# Schematic.net
KiCad netlist of a schematic drawn in EasyEDA
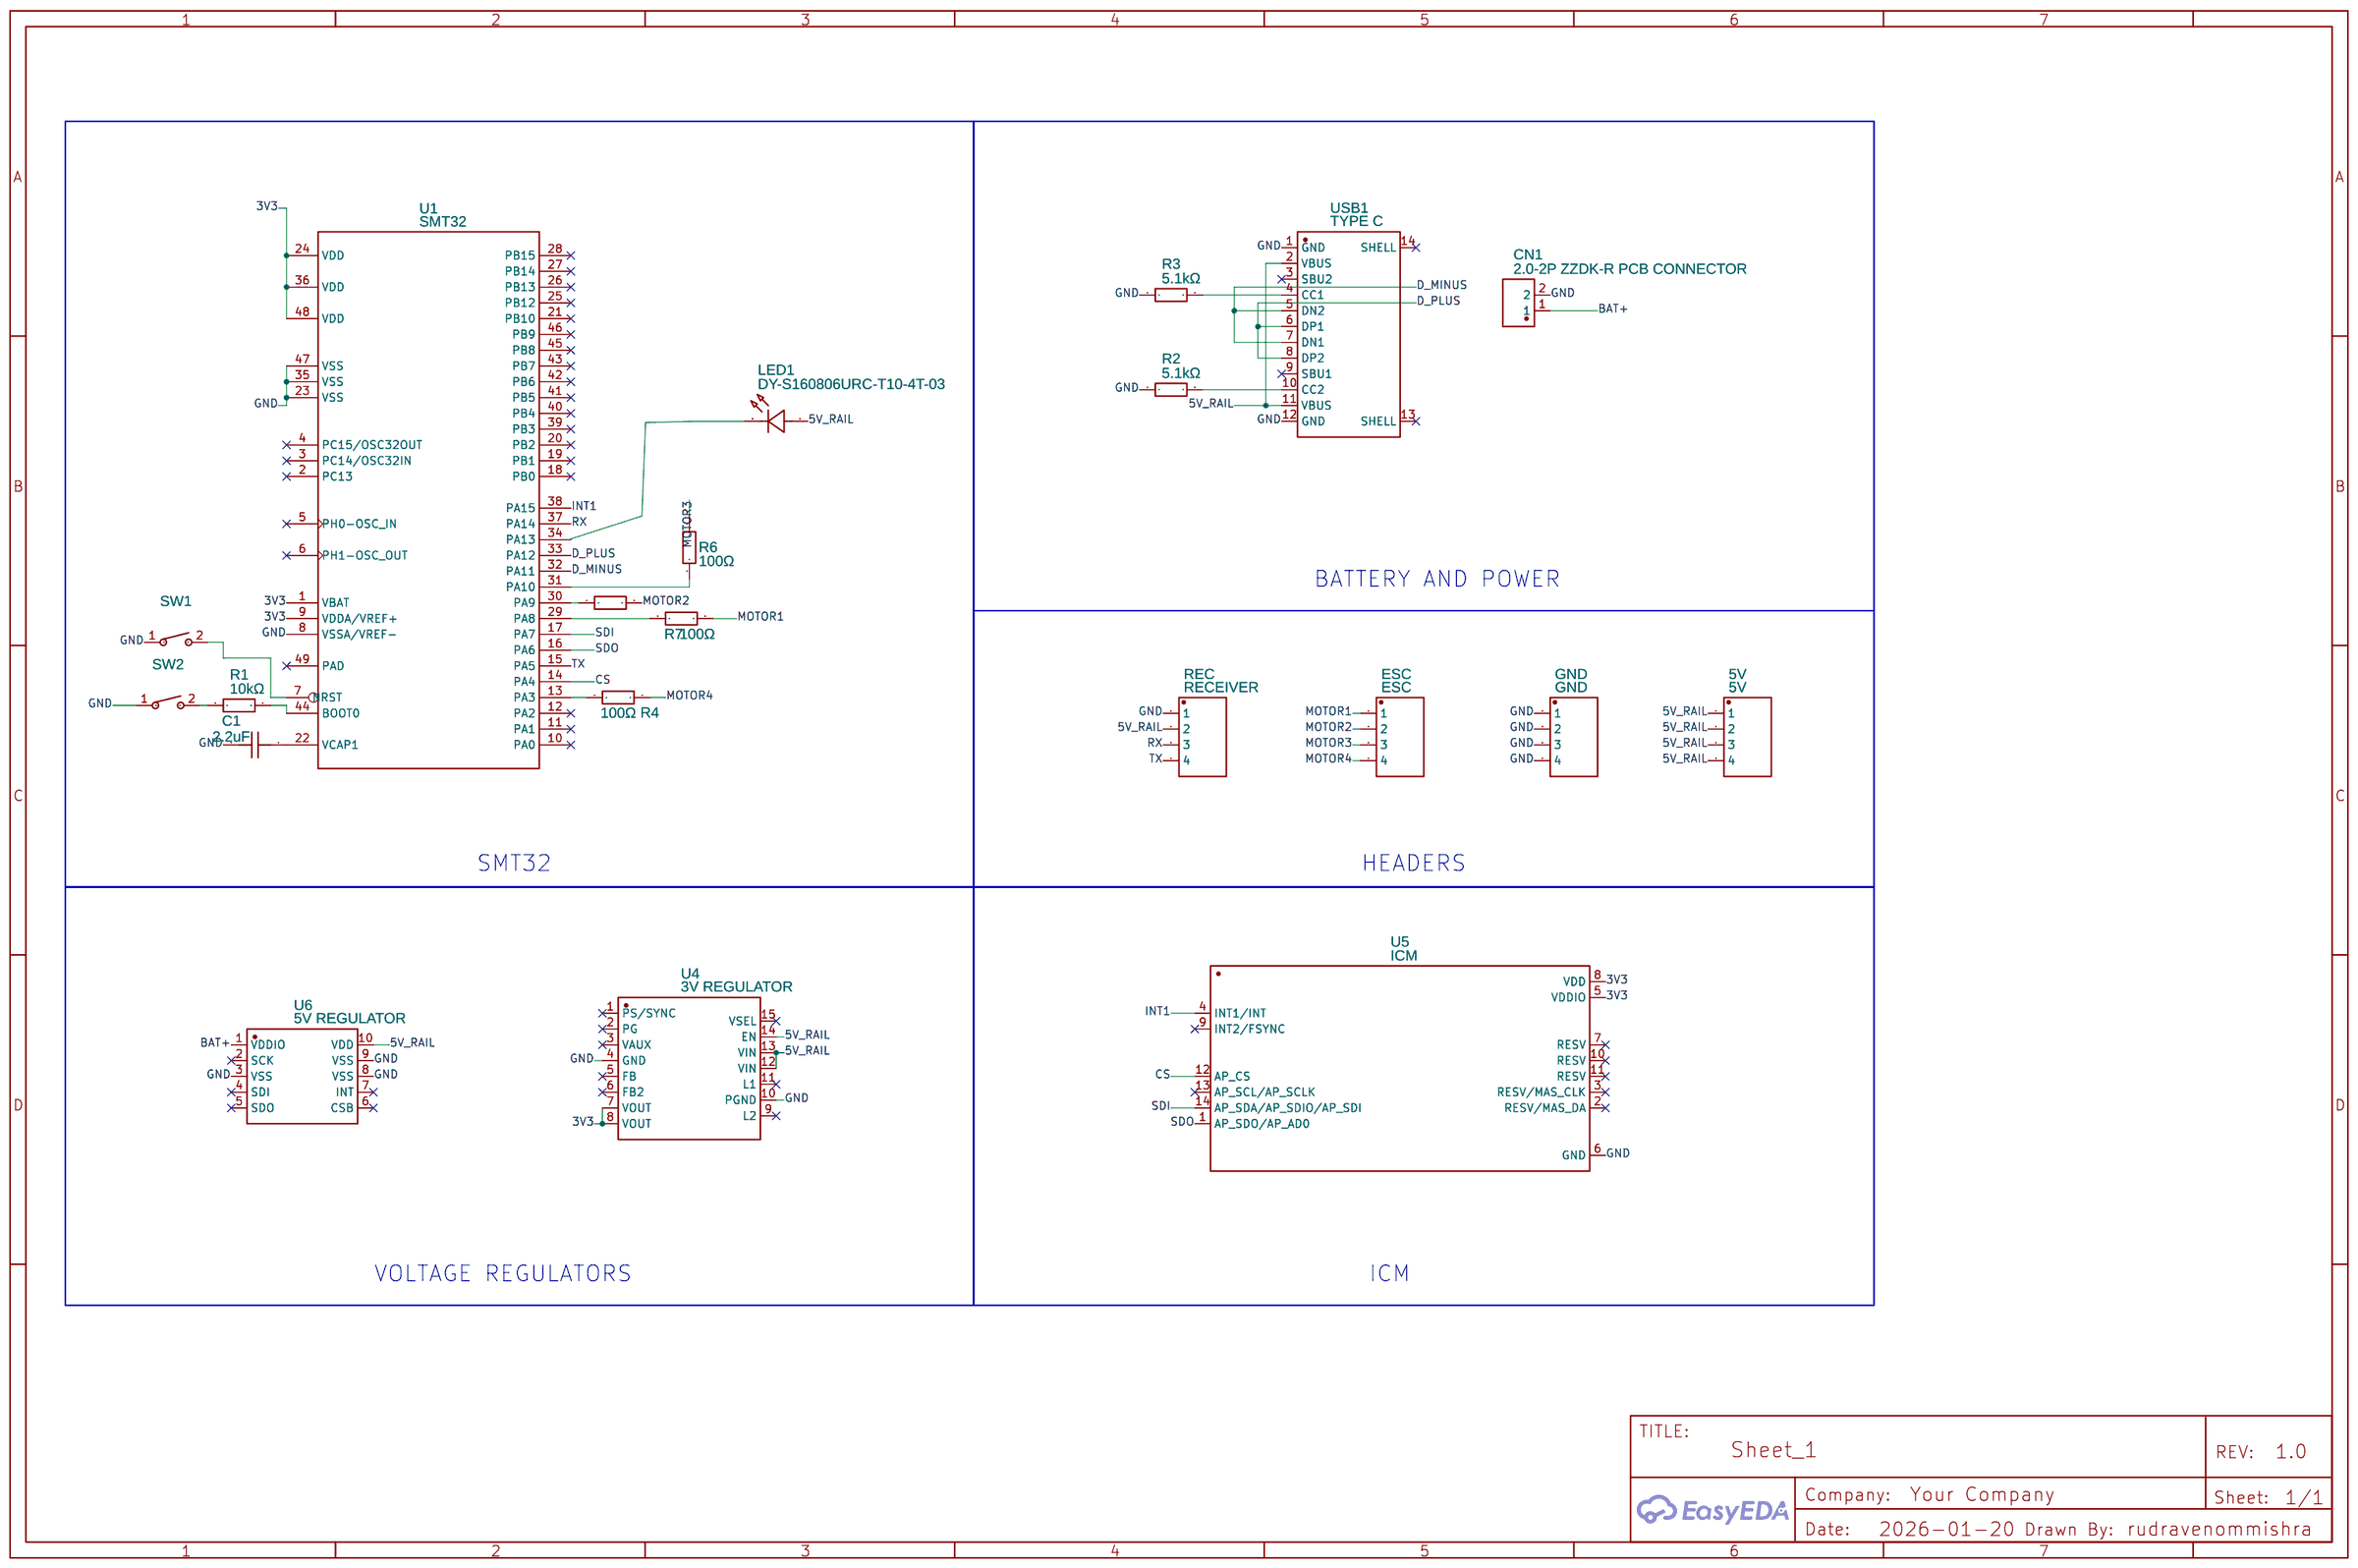
[diagram p0: schematic sheet]

(export (version "E")
  (design (tool "Eeschema 10.0.6"))
  (components
    (comp (ref "5V")
      (value "5V")
      (fields (field (name "Manufacturer Part") "B-2100S04P-A110") (field (name "Manufacturer") "Ckmtw(灿科盟)"))
      (libsource (lib "") (part "Header-Male-2.54_1x4"))
    )
    (comp (ref "C1")
      (value "2.2uF")
      (fields (field (name "Manufacturer Part") "1206X225K250NT") (field (name "Manufacturer") "FH(风华)"))
      (libsource (lib "") (part "1206X225K250NT"))
    )
    (comp (ref "CN1")
      (value "2.0-2P ZZDK-R PCB CONNECTOR")
      (fields
        (field (name "Manufacturer Part") "2.0-2P ZZDK-R PCB Connector")
        (field (name "Manufacturer") "SHOU HAN(首韩)")
      )
      (libsource (lib "") (part "2.0-2P ZZDK-R PCB CONNECTOR"))
    )
    (comp (ref "ESC")
      (value "ESC")
      (fields (field (name "Manufacturer Part") "B-2100S04P-A110") (field (name "Manufacturer") "Ckmtw(灿科盟)"))
      (libsource (lib "") (part "Header-Male-2.54_1x4_2"))
    )
    (comp (ref "GND")
      (value "GND")
      (fields (field (name "Manufacturer Part") "B-2100S04P-A110") (field (name "Manufacturer") "Ckmtw(灿科盟)"))
      (libsource (lib "") (part "Header-Male-2.54_1x4_1"))
    )
    (comp (ref "LED1")
      (value "DY-S160806URC-T10-4T-03")
      (fields (field (name "Manufacturer") "TONYU(东裕)"))
      (libsource (lib "") (part "DY-S160806URC-T10-4T-03"))
    )
    (comp (ref "R1")
      (value "10kΩ")
      (fields (field (name "Manufacturer Part") "PTFR0805B10K0P9") (field (name "Manufacturer") "RESI(开步睿思)"))
      (libsource (lib "") (part "PTFR0805B10K0P9"))
    )
    (comp (ref "R2")
      (value "5.1kΩ")
      (fields
        (field (name "Manufacturer Part") "0402WGF5101TCE")
        (field (name "Manufacturer") "UNI-ROYAL(厚声)")
      )
      (libsource (lib "") (part "0402WGF5101TCE"))
    )
    (comp (ref "R3")
      (value "5.1kΩ")
      (fields
        (field (name "Manufacturer Part") "0402WGF5101TCE")
        (field (name "Manufacturer") "UNI-ROYAL(厚声)")
      )
      (libsource (lib "") (part "0402WGF5101TCE"))
    )
    (comp (ref "R4")
      (value "100Ω")
      (fields
        (field (name "Manufacturer Part") "0105WHF1000TDE")
        (field (name "Manufacturer") "UNI-ROYAL(厚声)")
      )
      (libsource (lib "") (part "0105WHF1000TDE"))
    )
    (comp (ref "R5")
      (value "100Ω")
      (fields
        (field (name "Manufacturer Part") "0105WHF1000TDE")
        (field (name "Manufacturer") "UNI-ROYAL(厚声)")
      )
      (libsource (lib "") (part "0105WHF1000TDE"))
    )
    (comp (ref "R6")
      (value "100Ω")
      (fields
        (field (name "Manufacturer Part") "0105WHF1000TDE")
        (field (name "Manufacturer") "UNI-ROYAL(厚声)")
      )
      (libsource (lib "") (part "0105WHF1000TDE_1"))
    )
    (comp (ref "R7")
      (value "100Ω")
      (fields
        (field (name "Manufacturer Part") "0105WHF1000TDE")
        (field (name "Manufacturer") "UNI-ROYAL(厚声)")
      )
      (libsource (lib "") (part "0105WHF1000TDE"))
    )
    (comp (ref "REC")
      (value "RECEIVER")
      (fields (field (name "Manufacturer Part") "B-2100S04P-A110") (field (name "Manufacturer") "Ckmtw(灿科盟)"))
      (libsource (lib "") (part "Header-Male-2.54_1x4_3"))
    )
    (comp (ref "SW1")
      (value "HX 3X4X2-2P-1.6N TACTILE SWITCH")
      (fields
        (field (name "Manufacturer Part") "HX 3x4x2-2P-1.6N TACTILE SWITCH")
        (field (name "Manufacturer") "hanxia(韩下)")
      )
      (libsource (lib "") (part "HX 3X4X2-2P-1.6N TACTILE SWITCH"))
    )
    (comp (ref "SW2")
      (value "HX 3X4X2-2P-1.6N TACTILE SWITCH")
      (fields
        (field (name "Manufacturer Part") "HX 3x4x2-2P-1.6N TACTILE SWITCH")
        (field (name "Manufacturer") "hanxia(韩下)")
      )
      (libsource (lib "") (part "HX 3X4X2-2P-1.6N TACTILE SWITCH"))
    )
    (comp (ref "U1")
      (value "SMT32")
      (fields (field (name "Manufacturer Part") "STM32F411CEU6") (field (name "Manufacturer") "ST(意法半导体)"))
      (libsource (lib "") (part "STM32F411CEU6"))
    )
    (comp (ref "U4")
      (value "3V REGULATOR")
      (fields (field (name "Manufacturer Part") "TPS630701RNMR") (field (name "Manufacturer") "TI(德州仪器)"))
      (libsource (lib "") (part "TPS630701RNMR"))
    )
    (comp (ref "U5")
      (value "ICM")
      (fields
        (field (name "Manufacturer Part") "ICM-45605")
        (field (name "Manufacturer") "TDK InvenSense(应美盛)")
      )
      (libsource (lib "") (part "ICM-45605"))
    )
    (comp (ref "U6")
      (value "5V REGULATOR")
      (fields (field (name "Manufacturer Part") "BMP580") (field (name "Manufacturer") "Bosch(博世)"))
      (libsource (lib "") (part "BMP580"))
    )
    (comp (ref "USB1")
      (value "TYPE C")
      (fields
        (field (name "Manufacturer Part") "TYPE-C 16PIN 2MD(073)")
        (field (name "Manufacturer") "SHOU HAN(首韩)")
      )
      (libsource (lib "") (part "TYPE-C 16PIN 2MD(073)"))
    )
  )
  (nets
    (net (code "1") (name "/3V3") (class "Default")
      (node (ref "U1") (pin "1") (pinfunction "VBAT_1") (pintype "passive"))
      (node (ref "U1") (pin "24") (pinfunction "VDD_24") (pintype "unspecified"))
      (node (ref "U1") (pin "36") (pinfunction "VDD_36") (pintype "unspecified"))
      (node (ref "U1") (pin "48") (pinfunction "VDD_48") (pintype "unspecified"))
      (node (ref "U1") (pin "9") (pinfunction "VDDA/VREF+_9") (pintype "passive"))
      (node (ref "U4") (pin "7") (pinfunction "VOUT_7") (pintype "unspecified"))
      (node (ref "U4") (pin "8") (pinfunction "VOUT_8") (pintype "unspecified"))
      (node (ref "U5") (pin "5") (pinfunction "VDDIO_5") (pintype "unspecified"))
      (node (ref "U5") (pin "8") (pinfunction "VDD_8") (pintype "unspecified"))
    )
    (net (code "2") (name "/5V_RAIL") (class "Default")
      (node (ref "5V") (pin "1") (pinfunction "1_1") (pintype "unspecified"))
      (node (ref "5V") (pin "2") (pinfunction "2_2") (pintype "unspecified"))
      (node (ref "5V") (pin "3") (pinfunction "3_3") (pintype "unspecified"))
      (node (ref "5V") (pin "4") (pinfunction "4_4") (pintype "unspecified"))
      (node (ref "LED1") (pin "2") (pinfunction "A_2") (pintype "unspecified"))
      (node (ref "REC") (pin "2") (pinfunction "2_2") (pintype "unspecified"))
      (node (ref "U4") (pin "12") (pinfunction "VIN_12") (pintype "unspecified"))
      (node (ref "U4") (pin "13") (pinfunction "VIN_13") (pintype "unspecified"))
      (node (ref "U4") (pin "14") (pinfunction "EN_14") (pintype "unspecified"))
      (node (ref "U6") (pin "10") (pinfunction "VDD_10") (pintype "unspecified"))
      (node (ref "USB1") (pin "11") (pinfunction "VBUS_11") (pintype "unspecified"))
      (node (ref "USB1") (pin "2") (pinfunction "VBUS_2") (pintype "unspecified"))
    )
    (net (code "3") (name "/BAT+") (class "Default")
      (node (ref "CN1") (pin "1") (pinfunction "1_1") (pintype "unspecified"))
      (node (ref "U6") (pin "1") (pinfunction "VDDIO_1") (pintype "unspecified"))
    )
    (net (code "4") (name "/CS") (class "Default")
      (node (ref "U1") (pin "14") (pinfunction "PA4_14") (pintype "unspecified"))
      (node (ref "U5") (pin "12") (pinfunction "AP_CS_12") (pintype "unspecified"))
    )
    (net (code "5") (name "/D_MINUS") (class "Default")
      (node (ref "U1") (pin "32") (pinfunction "PA11_32") (pintype "unspecified"))
      (node (ref "USB1") (pin "5") (pinfunction "DN2_5") (pintype "unspecified"))
      (node (ref "USB1") (pin "7") (pinfunction "DN1_7") (pintype "unspecified"))
    )
    (net (code "6") (name "/D_PLUS") (class "Default")
      (node (ref "U1") (pin "33") (pinfunction "PA12_33") (pintype "unspecified"))
      (node (ref "USB1") (pin "6") (pinfunction "DP1_6") (pintype "unspecified"))
      (node (ref "USB1") (pin "8") (pinfunction "DP2_8") (pintype "unspecified"))
    )
    (net (code "7") (name "/GND") (class "Default")
      (node (ref "C1") (pin "1") (pinfunction "1_1") (pintype "unspecified"))
      (node (ref "CN1") (pin "2") (pinfunction "2_2") (pintype "unspecified"))
      (node (ref "GND") (pin "1") (pinfunction "1_1") (pintype "unspecified"))
      (node (ref "GND") (pin "2") (pinfunction "2_2") (pintype "unspecified"))
      (node (ref "GND") (pin "3") (pinfunction "3_3") (pintype "unspecified"))
      (node (ref "GND") (pin "4") (pinfunction "4_4") (pintype "unspecified"))
      (node (ref "R2") (pin "1") (pinfunction "1_1") (pintype "input"))
      (node (ref "R3") (pin "1") (pinfunction "1_1") (pintype "input"))
      (node (ref "REC") (pin "1") (pinfunction "1_1") (pintype "unspecified"))
      (node (ref "SW1") (pin "1") (pinfunction "1_1") (pintype "unspecified"))
      (node (ref "SW2") (pin "1") (pinfunction "1_1") (pintype "unspecified"))
      (node (ref "U1") (pin "23") (pinfunction "VSS_23") (pintype "unspecified"))
      (node (ref "U1") (pin "35") (pinfunction "VSS_35") (pintype "unspecified"))
      (node (ref "U1") (pin "47") (pinfunction "VSS_47") (pintype "unspecified"))
      (node (ref "U1") (pin "8") (pinfunction "VSSA/VREF-_8") (pintype "passive"))
      (node (ref "U4") (pin "10") (pinfunction "PGND_10") (pintype "unspecified"))
      (node (ref "U4") (pin "4") (pinfunction "GND_4") (pintype "unspecified"))
      (node (ref "U5") (pin "6") (pinfunction "GND_6") (pintype "unspecified"))
      (node (ref "U6") (pin "3") (pinfunction "VSS_3") (pintype "unspecified"))
      (node (ref "U6") (pin "8") (pinfunction "VSS_8") (pintype "unspecified"))
      (node (ref "U6") (pin "9") (pinfunction "VSS_9") (pintype "unspecified"))
      (node (ref "USB1") (pin "1") (pinfunction "GND_1") (pintype "unspecified"))
      (node (ref "USB1") (pin "12") (pinfunction "GND_12") (pintype "unspecified"))
    )
    (net (code "8") (name "/INT1") (class "Default")
      (node (ref "U1") (pin "38") (pinfunction "PA15_38") (pintype "unspecified"))
      (node (ref "U5") (pin "4") (pinfunction "INT1/INT_4") (pintype "unspecified"))
    )
    (net (code "9") (name "/MOTOR1") (class "Default")
      (node (ref "ESC") (pin "1") (pinfunction "1_1") (pintype "unspecified"))
      (node (ref "R7") (pin "2") (pinfunction "2_2") (pintype "unspecified"))
    )
    (net (code "10") (name "/MOTOR2") (class "Default")
      (node (ref "ESC") (pin "2") (pinfunction "2_2") (pintype "unspecified"))
      (node (ref "R5") (pin "2") (pinfunction "2_2") (pintype "unspecified"))
    )
    (net (code "11") (name "/MOTOR3") (class "Default")
      (node (ref "ESC") (pin "3") (pinfunction "3_3") (pintype "unspecified"))
      (node (ref "R6") (pin "2") (pinfunction "2_2") (pintype "unspecified"))
    )
    (net (code "12") (name "/MOTOR4") (class "Default")
      (node (ref "ESC") (pin "4") (pinfunction "4_4") (pintype "unspecified"))
      (node (ref "R4") (pin "2") (pinfunction "2_2") (pintype "unspecified"))
    )
    (net (code "13") (name "/RX") (class "Default")
      (node (ref "REC") (pin "3") (pinfunction "3_3") (pintype "unspecified"))
      (node (ref "U1") (pin "37") (pinfunction "PA14_37") (pintype "unspecified"))
    )
    (net (code "14") (name "/SDI") (class "Default")
      (node (ref "U1") (pin "17") (pinfunction "PA7_17") (pintype "unspecified"))
      (node (ref "U5") (pin "14") (pinfunction "AP_SDA/AP_SDIO/AP_SDI_14") (pintype "unspecified"))
    )
    (net (code "15") (name "/SDO") (class "Default")
      (node (ref "U1") (pin "16") (pinfunction "PA6_16") (pintype "unspecified"))
      (node (ref "U5") (pin "1") (pinfunction "AP_SDO/AP_AD0_1") (pintype "unspecified"))
    )
    (net (code "16") (name "/TX") (class "Default")
      (node (ref "REC") (pin "4") (pinfunction "4_4") (pintype "unspecified"))
      (node (ref "U1") (pin "15") (pinfunction "PA5_15") (pintype "unspecified"))
    )
    (net (code "17") (name "Net-(LED1-K)") (class "Default")
      (node (ref "LED1") (pin "1") (pinfunction "K_1") (pintype "unspecified"))
      (node (ref "U1") (pin "34") (pinfunction "PA13_34") (pintype "unspecified"))
    )
    (net (code "18") (name "Net-(R1-Pad1)") (class "Default")
      (node (ref "R1") (pin "1") (pinfunction "1_1") (pintype "input"))
      (node (ref "SW2") (pin "2") (pinfunction "2_2") (pintype "unspecified"))
    )
    (net (code "19") (name "Net-(U1-BOOT0)") (class "Default")
      (node (ref "R1") (pin "2") (pinfunction "2_2") (pintype "input"))
      (node (ref "U1") (pin "44") (pinfunction "BOOT0_44") (pintype "input"))
    )
    (net (code "20") (name "Net-(U1-NRST)") (class "Default")
      (node (ref "SW1") (pin "2") (pinfunction "2_2") (pintype "unspecified"))
      (node (ref "U1") (pin "7") (pinfunction "NRST_7") (pintype "unspecified"))
    )
    (net (code "21") (name "Net-(U1-PA3)") (class "Default")
      (node (ref "R4") (pin "1") (pinfunction "1_1") (pintype "unspecified"))
      (node (ref "U1") (pin "13") (pinfunction "PA3_13") (pintype "unspecified"))
    )
    (net (code "22") (name "Net-(U1-PA8)") (class "Default")
      (node (ref "R7") (pin "1") (pinfunction "1_1") (pintype "unspecified"))
      (node (ref "U1") (pin "29") (pinfunction "PA8_29") (pintype "unspecified"))
    )
    (net (code "23") (name "Net-(U1-PA9)") (class "Default")
      (node (ref "R5") (pin "1") (pinfunction "1_1") (pintype "unspecified"))
      (node (ref "U1") (pin "30") (pinfunction "PA9_30") (pintype "unspecified"))
    )
    (net (code "24") (name "Net-(U1-PA10)") (class "Default")
      (node (ref "R6") (pin "1") (pinfunction "1_1") (pintype "unspecified"))
      (node (ref "U1") (pin "31") (pinfunction "PA10_31") (pintype "unspecified"))
    )
    (net (code "25") (name "Net-(U1-VCAP1)") (class "Default")
      (node (ref "C1") (pin "2") (pinfunction "2_2") (pintype "unspecified"))
      (node (ref "U1") (pin "22") (pinfunction "VCAP1_22") (pintype "passive"))
    )
    (net (code "26") (name "Net-(USB1-CC1)") (class "Default")
      (node (ref "R3") (pin "2") (pinfunction "2_2") (pintype "input"))
      (node (ref "USB1") (pin "4") (pinfunction "CC1_4") (pintype "unspecified"))
    )
    (net (code "27") (name "Net-(USB1-CC2)") (class "Default")
      (node (ref "R2") (pin "2") (pinfunction "2_2") (pintype "input"))
      (node (ref "USB1") (pin "10") (pinfunction "CC2_10") (pintype "unspecified"))
    )
    (net (code "28") (name "unconnected-(U1-PA0-Pad10)") (class "Default")
      (node (ref "U1") (pin "10") (pinfunction "PA0_10") (pintype "unspecified+no_connect"))
    )
    (net (code "29") (name "unconnected-(U1-PA1-Pad11)") (class "Default")
      (node (ref "U1") (pin "11") (pinfunction "PA1_11") (pintype "unspecified+no_connect"))
    )
    (net (code "30") (name "unconnected-(U1-PA2-Pad12)") (class "Default")
      (node (ref "U1") (pin "12") (pinfunction "PA2_12") (pintype "unspecified+no_connect"))
    )
    (net (code "31") (name "unconnected-(U1-PAD-Pad49)") (class "Default")
      (node (ref "U1") (pin "49") (pinfunction "PAD_49") (pintype "passive+no_connect"))
    )
    (net (code "32") (name "unconnected-(U1-PB0-Pad18)") (class "Default")
      (node (ref "U1") (pin "18") (pinfunction "PB0_18") (pintype "unspecified+no_connect"))
    )
    (net (code "33") (name "unconnected-(U1-PB1-Pad19)") (class "Default")
      (node (ref "U1") (pin "19") (pinfunction "PB1_19") (pintype "unspecified+no_connect"))
    )
    (net (code "34") (name "unconnected-(U1-PB2-Pad20)") (class "Default")
      (node (ref "U1") (pin "20") (pinfunction "PB2_20") (pintype "unspecified+no_connect"))
    )
    (net (code "35") (name "unconnected-(U1-PB3-Pad39)") (class "Default")
      (node (ref "U1") (pin "39") (pinfunction "PB3_39") (pintype "unspecified+no_connect"))
    )
    (net (code "36") (name "unconnected-(U1-PB4-Pad40)") (class "Default")
      (node (ref "U1") (pin "40") (pinfunction "PB4_40") (pintype "unspecified+no_connect"))
    )
    (net (code "37") (name "unconnected-(U1-PB5-Pad41)") (class "Default")
      (node (ref "U1") (pin "41") (pinfunction "PB5_41") (pintype "unspecified+no_connect"))
    )
    (net (code "38") (name "unconnected-(U1-PB6-Pad42)") (class "Default")
      (node (ref "U1") (pin "42") (pinfunction "PB6_42") (pintype "unspecified+no_connect"))
    )
    (net (code "39") (name "unconnected-(U1-PB7-Pad43)") (class "Default")
      (node (ref "U1") (pin "43") (pinfunction "PB7_43") (pintype "unspecified+no_connect"))
    )
    (net (code "40") (name "unconnected-(U1-PB8-Pad45)") (class "Default")
      (node (ref "U1") (pin "45") (pinfunction "PB8_45") (pintype "unspecified+no_connect"))
    )
    (net (code "41") (name "unconnected-(U1-PB9-Pad46)") (class "Default")
      (node (ref "U1") (pin "46") (pinfunction "PB9_46") (pintype "unspecified+no_connect"))
    )
    (net (code "42") (name "unconnected-(U1-PB10-Pad21)") (class "Default")
      (node (ref "U1") (pin "21") (pinfunction "PB10_21") (pintype "unspecified+no_connect"))
    )
    (net (code "43") (name "unconnected-(U1-PB12-Pad25)") (class "Default")
      (node (ref "U1") (pin "25") (pinfunction "PB12_25") (pintype "unspecified+no_connect"))
    )
    (net (code "44") (name "unconnected-(U1-PB13-Pad26)") (class "Default")
      (node (ref "U1") (pin "26") (pinfunction "PB13_26") (pintype "unspecified+no_connect"))
    )
    (net (code "45") (name "unconnected-(U1-PB14-Pad27)") (class "Default")
      (node (ref "U1") (pin "27") (pinfunction "PB14_27") (pintype "unspecified+no_connect"))
    )
    (net (code "46") (name "unconnected-(U1-PB15-Pad28)") (class "Default")
      (node (ref "U1") (pin "28") (pinfunction "PB15_28") (pintype "unspecified+no_connect"))
    )
    (net (code "47") (name "unconnected-(U1-PC13-Pad2)") (class "Default")
      (node (ref "U1") (pin "2") (pinfunction "PC13_2") (pintype "unspecified+no_connect"))
    )
    (net (code "48") (name "unconnected-(U1-PC14{slash}OSC32IN-Pad3)") (class "Default")
      (node (ref "U1") (pin "3") (pinfunction "PC14/OSC32IN_3") (pintype "unspecified+no_connect"))
    )
    (net (code "49") (name "unconnected-(U1-PC15{slash}OSC32OUT-Pad4)") (class "Default")
      (node (ref "U1") (pin "4") (pinfunction "PC15/OSC32OUT_4") (pintype "unspecified+no_connect"))
    )
    (net (code "50") (name "unconnected-(U1-PH0-OSC_IN-Pad5)") (class "Default")
      (node (ref "U1") (pin "5") (pinfunction "PH0-OSC_IN_5") (pintype "unspecified+no_connect"))
    )
    (net (code "51") (name "unconnected-(U1-PH1-OSC_OUT-Pad6)") (class "Default")
      (node (ref "U1") (pin "6") (pinfunction "PH1-OSC_OUT_6") (pintype "unspecified+no_connect"))
    )
    (net (code "52") (name "unconnected-(U4-FB-Pad5)") (class "Default")
      (node (ref "U4") (pin "5") (pinfunction "FB_5") (pintype "unspecified+no_connect"))
    )
    (net (code "53") (name "unconnected-(U4-FB2-Pad6)") (class "Default")
      (node (ref "U4") (pin "6") (pinfunction "FB2_6") (pintype "unspecified+no_connect"))
    )
    (net (code "54") (name "unconnected-(U4-L1-Pad11)") (class "Default")
      (node (ref "U4") (pin "11") (pinfunction "L1_11") (pintype "unspecified+no_connect"))
    )
    (net (code "55") (name "unconnected-(U4-L2-Pad9)") (class "Default")
      (node (ref "U4") (pin "9") (pinfunction "L2_9") (pintype "unspecified+no_connect"))
    )
    (net (code "56") (name "unconnected-(U4-PG-Pad2)") (class "Default")
      (node (ref "U4") (pin "2") (pinfunction "PG_2") (pintype "unspecified+no_connect"))
    )
    (net (code "57") (name "unconnected-(U4-PS{slash}SYNC-Pad1)") (class "Default")
      (node (ref "U4") (pin "1") (pinfunction "PS/SYNC_1") (pintype "unspecified+no_connect"))
    )
    (net (code "58") (name "unconnected-(U4-VAUX-Pad3)") (class "Default")
      (node (ref "U4") (pin "3") (pinfunction "VAUX_3") (pintype "unspecified+no_connect"))
    )
    (net (code "59") (name "unconnected-(U4-VSEL-Pad15)") (class "Default")
      (node (ref "U4") (pin "15") (pinfunction "VSEL_15") (pintype "unspecified+no_connect"))
    )
    (net (code "60") (name "unconnected-(U5-AP_SCL{slash}AP_SCLK-Pad13)") (class "Default")
      (node (ref "U5") (pin "13") (pinfunction "AP_SCL/AP_SCLK_13") (pintype "unspecified+no_connect"))
    )
    (net (code "61") (name "unconnected-(U5-INT2{slash}FSYNC-Pad9)") (class "Default")
      (node (ref "U5") (pin "9") (pinfunction "INT2/FSYNC_9") (pintype "unspecified+no_connect"))
    )
    (net (code "62") (name "unconnected-(U5-RESV-Pad7)") (class "Default")
      (node (ref "U5") (pin "7") (pinfunction "RESV_7") (pintype "unspecified+no_connect"))
    )
    (net (code "63") (name "unconnected-(U5-RESV-Pad10)") (class "Default")
      (node (ref "U5") (pin "10") (pinfunction "RESV_10") (pintype "unspecified+no_connect"))
    )
    (net (code "64") (name "unconnected-(U5-RESV-Pad11)") (class "Default")
      (node (ref "U5") (pin "11") (pinfunction "RESV_11") (pintype "unspecified+no_connect"))
    )
    (net (code "65") (name "unconnected-(U5-RESV{slash}MAS_CLK-Pad3)") (class "Default")
      (node (ref "U5") (pin "3") (pinfunction "RESV/MAS_CLK_3") (pintype "unspecified+no_connect"))
    )
    (net (code "66") (name "unconnected-(U5-RESV{slash}MAS_DA-Pad2)") (class "Default")
      (node (ref "U5") (pin "2") (pinfunction "RESV/MAS_DA_2") (pintype "unspecified+no_connect"))
    )
    (net (code "67") (name "unconnected-(U6-CSB-Pad6)") (class "Default")
      (node (ref "U6") (pin "6") (pinfunction "CSB_6") (pintype "unspecified+no_connect"))
    )
    (net (code "68") (name "unconnected-(U6-INT-Pad7)") (class "Default")
      (node (ref "U6") (pin "7") (pinfunction "INT_7") (pintype "unspecified+no_connect"))
    )
    (net (code "69") (name "unconnected-(U6-SCK-Pad2)") (class "Default")
      (node (ref "U6") (pin "2") (pinfunction "SCK_2") (pintype "unspecified+no_connect"))
    )
    (net (code "70") (name "unconnected-(U6-SDI-Pad4)") (class "Default")
      (node (ref "U6") (pin "4") (pinfunction "SDI_4") (pintype "unspecified+no_connect"))
    )
    (net (code "71") (name "unconnected-(U6-SDO-Pad5)") (class "Default")
      (node (ref "U6") (pin "5") (pinfunction "SDO_5") (pintype "unspecified+no_connect"))
    )
    (net (code "72") (name "unconnected-(USB1-SBU1-Pad9)") (class "Default")
      (node (ref "USB1") (pin "9") (pinfunction "SBU1_9") (pintype "unspecified+no_connect"))
    )
    (net (code "73") (name "unconnected-(USB1-SBU2-Pad3)") (class "Default")
      (node (ref "USB1") (pin "3") (pinfunction "SBU2_3") (pintype "unspecified+no_connect"))
    )
    (net (code "74") (name "unconnected-(USB1-SHELL-Pad13)") (class "Default")
      (node (ref "USB1") (pin "13") (pinfunction "SHELL_13") (pintype "unspecified+no_connect"))
    )
    (net (code "75") (name "unconnected-(USB1-SHELL-Pad14)") (class "Default")
      (node (ref "USB1") (pin "14") (pinfunction "SHELL_14") (pintype "unspecified+no_connect"))
    )
  )
)
